# design.net
KiCad netlist of a schematic drawn in Altium Designer
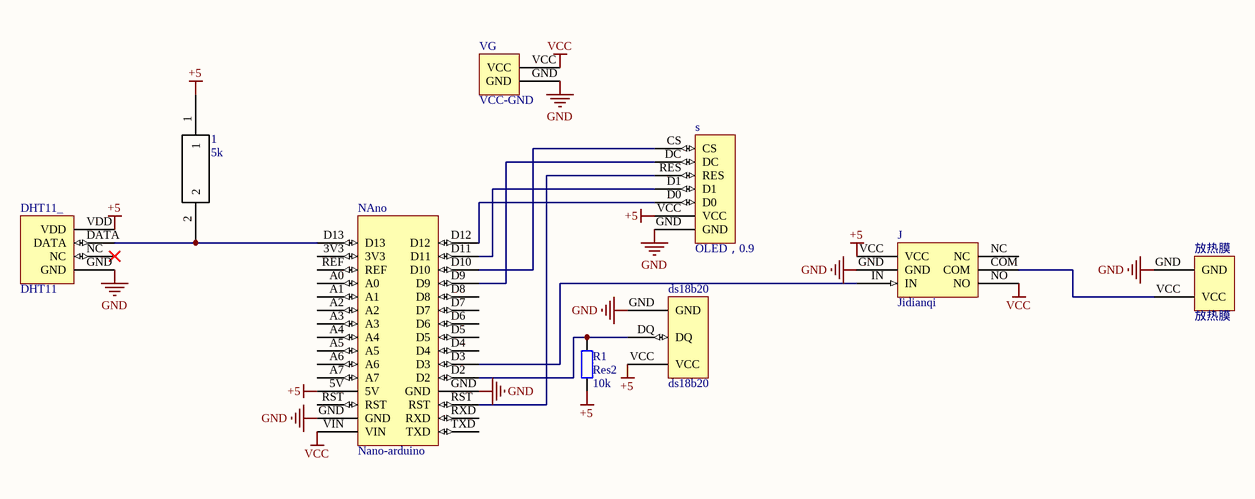
[diagram p0: 继电器版本.SchDoc]

(export (version "E")
  (design (tool "Eeschema 10.0.6"))
  (components
    (comp (ref "1") (value "5k") (footprint "51ou") (libsource (lib "Schlib1") (part "51ou")))
    (comp (ref "DHT11_") (value "DHT11") (footprint "DHT11") (libsource (lib "Schlib1") (part "DHT11")))
    (comp (ref "ds18b20")
      (value "ds18b20")
      (footprint "ds18b20")
      (libsource (lib "Schlib1") (part "ds18b20"))
    )
    (comp (ref "J") (value "Jidianqi") (footprint "Jidianqi") (libsource (lib "Schlib1") (part "Jidianqi")))
    (comp (ref "NAno")
      (value "Nano-arduino")
      (footprint "Nano")
      (libsource (lib "Schlib1") (part "Nano-arduino"))
    )
    (comp (ref "R1")
      (value "Res2")
      (footprint "AXIAL-0.4")
      (description "Resistor")
      (fields (field (name "ALTIUM_VALUE") "10k") (field (name "PUBLISHER") "Altium Limited"))
      (libsource (lib "Miscellaneous Devices") (part "Res2"))
    )
    (comp (ref "s") (value "OLED，0.9") (footprint "OLED 0.9") (libsource (lib "Schlib1") (part "OLED，0.9")))
    (comp (ref "VG") (value "VCC-GND") (footprint "VCC-gnd") (libsource (lib "Schlib1") (part "VCC-GND")))
    (comp (ref "放热膜") (value "放热膜") (footprint "hit-pic") (libsource (lib "Schlib1") (part "放热膜")))
  )
  (nets
    (net (code "1") (name "+5") (class "Default")
      (node (ref "1") (pin "1") (pinfunction "1_1") (pintype "power_in"))
      (node (ref "DHT11_") (pin "VDD") (pinfunction "VDD_VDD") (pintype "power_in"))
      (node (ref "J") (pin "VCC") (pinfunction "VCC_VCC") (pintype "power_in"))
      (node (ref "NAno") (pin "5V") (pinfunction "5V_5V") (pintype "power_in"))
      (node (ref "R1") (pin "1") (pinfunction "1_1") (pintype "passive"))
      (node (ref "ds18b20") (pin "VCC") (pinfunction "VCC_VCC") (pintype "power_in"))
      (node (ref "s") (pin "VCC") (pinfunction "VCC_VCC") (pintype "power_in"))
    )
    (net (code "2") (name "GND") (class "Default")
      (node (ref "DHT11_") (pin "GND") (pinfunction "GND_GND") (pintype "power_in"))
      (node (ref "J") (pin "GND") (pinfunction "GND_GND") (pintype "power_in"))
      (node (ref "NAno") (pin "GND") (pinfunction "GND_GND") (pintype "power_in"))
      (node (ref "VG") (pin "GND") (pinfunction "GND_GND") (pintype "power_in"))
      (node (ref "ds18b20") (pin "GND") (pinfunction "GND_GND") (pintype "power_in"))
      (node (ref "s") (pin "GND") (pinfunction "GND_GND") (pintype "power_in"))
      (node (ref "放热膜") (pin "GND") (pinfunction "GND_GND") (pintype "power_in"))
    )
    (net (code "3") (name "Net-(1-Pad2)") (class "Default")
      (node (ref "1") (pin "2") (pinfunction "2_2") (pintype "power_in"))
      (node (ref "DHT11_") (pin "DATA") (pinfunction "DATA_DATA") (pintype "bidirectional"))
      (node (ref "NAno") (pin "D13") (pinfunction "D13_D13") (pintype "bidirectional"))
    )
    (net (code "4") (name "Net-(J-PadCOM)") (class "Default")
      (node (ref "J") (pin "COM") (pinfunction "COM_COM") (pintype "power_in"))
      (node (ref "放热膜") (pin "VCC") (pinfunction "VCC_VCC") (pintype "power_in"))
    )
    (net (code "5") (name "Net-(J-PadIN)") (class "Default")
      (node (ref "J") (pin "IN") (pinfunction "IN_IN") (pintype "input"))
      (node (ref "NAno") (pin "D3") (pinfunction "D3_D3") (pintype "bidirectional"))
    )
    (net (code "6") (name "Net-(NAno-PadD2)") (class "Default")
      (node (ref "NAno") (pin "D2") (pinfunction "D2_D2") (pintype "bidirectional"))
      (node (ref "R1") (pin "2") (pinfunction "2_2") (pintype "passive"))
      (node (ref "ds18b20") (pin "DQ") (pinfunction "DQ_DQ") (pintype "bidirectional"))
    )
    (net (code "7") (name "Net-(NAno-PadD9)") (class "Default")
      (node (ref "NAno") (pin "D9") (pinfunction "D9_D9") (pintype "bidirectional"))
      (node (ref "s") (pin "DC") (pinfunction "DC_DC") (pintype "bidirectional"))
    )
    (net (code "8") (name "Net-(NAno-PadD10)") (class "Default")
      (node (ref "NAno") (pin "D10") (pinfunction "D10_D10") (pintype "bidirectional"))
      (node (ref "s") (pin "CS") (pinfunction "CS_CS") (pintype "bidirectional"))
    )
    (net (code "9") (name "Net-(NAno-PadD11)") (class "Default")
      (node (ref "NAno") (pin "D11") (pinfunction "D11_D11") (pintype "bidirectional"))
      (node (ref "s") (pin "D1") (pinfunction "D1_D1") (pintype "bidirectional"))
    )
    (net (code "10") (name "Net-(NAno-PadD12)") (class "Default")
      (node (ref "NAno") (pin "D12") (pinfunction "D12_D12") (pintype "bidirectional"))
      (node (ref "s") (pin "D0") (pinfunction "D0_D0") (pintype "bidirectional"))
    )
    (net (code "11") (name "Net-(NAno-PadRST)_1") (class "Default")
      (node (ref "NAno") (pin "RST") (pinfunction "RST_RST") (pintype "bidirectional"))
      (node (ref "s") (pin "RES") (pinfunction "RES_RES") (pintype "bidirectional"))
    )
    (net (code "12") (name "VCC") (class "Default")
      (node (ref "J") (pin "NO") (pinfunction "NO_NO") (pintype "power_in"))
      (node (ref "NAno") (pin "VIN") (pinfunction "VIN_VIN") (pintype "power_in"))
      (node (ref "VG") (pin "VCC") (pinfunction "VCC_VCC") (pintype "power_in"))
    )
    (net (code "13") (name "unconnected-(DHT11_-PadNC)") (class "Default")
      (node (ref "DHT11_") (pin "NC") (pinfunction "NC_NC") (pintype "bidirectional+no_connect"))
    )
    (net (code "14") (name "unconnected-(J-PadNC)") (class "Default")
      (node (ref "J") (pin "NC") (pinfunction "NC_NC") (pintype "power_in"))
    )
    (net (code "15") (name "unconnected-(NAno-Pad3V3)") (class "Default")
      (node (ref "NAno") (pin "3V3") (pinfunction "3V3_3V3") (pintype "bidirectional"))
    )
    (net (code "16") (name "unconnected-(NAno-PadA0)") (class "Default")
      (node (ref "NAno") (pin "A0") (pinfunction "A0_A0") (pintype "bidirectional"))
    )
    (net (code "17") (name "unconnected-(NAno-PadA1)") (class "Default")
      (node (ref "NAno") (pin "A1") (pinfunction "A1_A1") (pintype "bidirectional"))
    )
    (net (code "18") (name "unconnected-(NAno-PadA2)") (class "Default")
      (node (ref "NAno") (pin "A2") (pinfunction "A2_A2") (pintype "bidirectional"))
    )
    (net (code "19") (name "unconnected-(NAno-PadA3)") (class "Default")
      (node (ref "NAno") (pin "A3") (pinfunction "A3_A3") (pintype "bidirectional"))
    )
    (net (code "20") (name "unconnected-(NAno-PadA4)") (class "Default")
      (node (ref "NAno") (pin "A4") (pinfunction "A4_A4") (pintype "bidirectional"))
    )
    (net (code "21") (name "unconnected-(NAno-PadA5)") (class "Default")
      (node (ref "NAno") (pin "A5") (pinfunction "A5_A5") (pintype "bidirectional"))
    )
    (net (code "22") (name "unconnected-(NAno-PadA6)") (class "Default")
      (node (ref "NAno") (pin "A6") (pinfunction "A6_A6") (pintype "bidirectional"))
    )
    (net (code "23") (name "unconnected-(NAno-PadA7)") (class "Default")
      (node (ref "NAno") (pin "A7") (pinfunction "A7_A7") (pintype "bidirectional"))
    )
    (net (code "24") (name "unconnected-(NAno-PadD4)") (class "Default")
      (node (ref "NAno") (pin "D4") (pinfunction "D4_D4") (pintype "bidirectional"))
    )
    (net (code "25") (name "unconnected-(NAno-PadD5)") (class "Default")
      (node (ref "NAno") (pin "D5") (pinfunction "D5_D5") (pintype "bidirectional"))
    )
    (net (code "26") (name "unconnected-(NAno-PadD6)") (class "Default")
      (node (ref "NAno") (pin "D6") (pinfunction "D6_D6") (pintype "bidirectional"))
    )
    (net (code "27") (name "unconnected-(NAno-PadD7)") (class "Default")
      (node (ref "NAno") (pin "D7") (pinfunction "D7_D7") (pintype "bidirectional"))
    )
    (net (code "28") (name "unconnected-(NAno-PadD8)") (class "Default")
      (node (ref "NAno") (pin "D8") (pinfunction "D8_D8") (pintype "bidirectional"))
    )
    (net (code "29") (name "unconnected-(NAno-PadREF)") (class "Default")
      (node (ref "NAno") (pin "REF") (pinfunction "REF_REF") (pintype "bidirectional"))
    )
    (net (code "30") (name "unconnected-(NAno-PadRST)") (class "Default")
      (node (ref "NAno") (pin "RST") (pinfunction "RST_RST") (pintype "bidirectional"))
    )
    (net (code "31") (name "unconnected-(NAno-PadRXD)") (class "Default")
      (node (ref "NAno") (pin "RXD") (pinfunction "RXD_RXD") (pintype "bidirectional"))
    )
    (net (code "32") (name "unconnected-(NAno-PadTXD)") (class "Default")
      (node (ref "NAno") (pin "TXD") (pinfunction "TXD_TXD") (pintype "bidirectional"))
    )
  )
)
